# vyndej.net
KiCad netlist of a schematic drawn in EAGLE
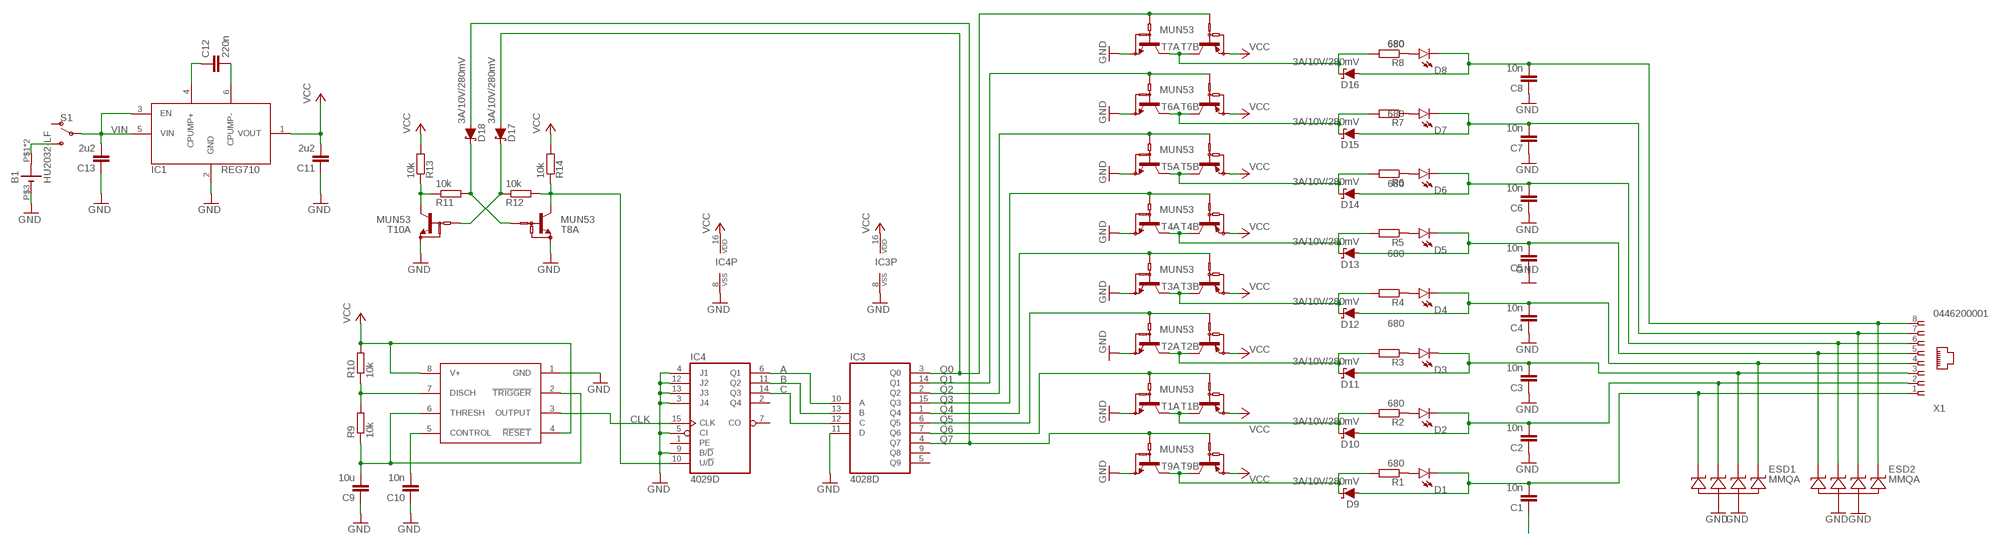
[diagram p0: schematic, sheet 1]

(export (version "E")
  (design (tool "Eeschema 10.0.6"))
  (components
    (comp (ref "B1")
      (value "HU2032-LF")
      (footprint "eagle-import:HU2032-LF")
      (libsource (lib "eagle-import") (part "HU2032-LF"))
    )
    (comp (ref "C1")
      (value "10n")
      (footprint "eagle-import:C0603")
      (libsource (lib "eagle-import") (part "C-EUC0603"))
    )
    (comp (ref "C2")
      (value "10n")
      (footprint "eagle-import:C0603")
      (libsource (lib "eagle-import") (part "C-EUC0603"))
    )
    (comp (ref "C3")
      (value "10n")
      (footprint "eagle-import:C0603")
      (libsource (lib "eagle-import") (part "C-EUC0603"))
    )
    (comp (ref "C4")
      (value "10n")
      (footprint "eagle-import:C0603")
      (libsource (lib "eagle-import") (part "C-EUC0603"))
    )
    (comp (ref "C5")
      (value "10n")
      (footprint "eagle-import:C0603")
      (libsource (lib "eagle-import") (part "C-EUC0603"))
    )
    (comp (ref "C6")
      (value "10n")
      (footprint "eagle-import:C0603")
      (libsource (lib "eagle-import") (part "C-EUC0603"))
    )
    (comp (ref "C7")
      (value "10n")
      (footprint "eagle-import:C0603")
      (libsource (lib "eagle-import") (part "C-EUC0603"))
    )
    (comp (ref "C8")
      (value "10n")
      (footprint "eagle-import:C0603")
      (libsource (lib "eagle-import") (part "C-EUC0603"))
    )
    (comp (ref "C9")
      (value "10u")
      (footprint "eagle-import:C1210K")
      (libsource (lib "eagle-import") (part "C-EUC1210K"))
    )
    (comp (ref "C10")
      (value "10n")
      (footprint "eagle-import:C0603")
      (libsource (lib "eagle-import") (part "C-EUC0603"))
    )
    (comp (ref "C11")
      (value "2u2")
      (footprint "eagle-import:C0603")
      (libsource (lib "eagle-import") (part "C-EUC0603"))
    )
    (comp (ref "C12")
      (value "220n")
      (footprint "eagle-import:C0603")
      (libsource (lib "eagle-import") (part "C-EUC0603"))
    )
    (comp (ref "C13")
      (value "2u2")
      (footprint "eagle-import:C0603")
      (libsource (lib "eagle-import") (part "C-EUC0603"))
    )
    (comp (ref "D1")
      (value "RED")
      (footprint "eagle-import:PLCC-2")
      (libsource (lib "eagle-import") (part "LED"))
    )
    (comp (ref "D2")
      (value "RED")
      (footprint "eagle-import:PLCC-2")
      (libsource (lib "eagle-import") (part "LED"))
    )
    (comp (ref "D3")
      (value "RED")
      (footprint "eagle-import:PLCC-2")
      (libsource (lib "eagle-import") (part "LED"))
    )
    (comp (ref "D4")
      (value "RED")
      (footprint "eagle-import:PLCC-2")
      (libsource (lib "eagle-import") (part "LED"))
    )
    (comp (ref "D5")
      (value "RED")
      (footprint "eagle-import:PLCC-2")
      (libsource (lib "eagle-import") (part "LED"))
    )
    (comp (ref "D6")
      (value "RED")
      (footprint "eagle-import:PLCC-2")
      (libsource (lib "eagle-import") (part "LED"))
    )
    (comp (ref "D7")
      (value "RED")
      (footprint "eagle-import:PLCC-2")
      (libsource (lib "eagle-import") (part "LED"))
    )
    (comp (ref "D8")
      (value "RED")
      (footprint "eagle-import:PLCC-2")
      (libsource (lib "eagle-import") (part "LED"))
    )
    (comp (ref "D9")
      (value "3A/10V/280mV")
      (footprint "eagle-import:SOD-323")
      (libsource (lib "eagle-import") (part "DIODE-SCHOTTKY-BAT60A"))
    )
    (comp (ref "D10")
      (value "3A/10V/280mV")
      (footprint "eagle-import:SOD-323")
      (libsource (lib "eagle-import") (part "DIODE-SCHOTTKY-BAT60A"))
    )
    (comp (ref "D11")
      (value "3A/10V/280mV")
      (footprint "eagle-import:SOD-323")
      (libsource (lib "eagle-import") (part "DIODE-SCHOTTKY-BAT60A"))
    )
    (comp (ref "D12")
      (value "3A/10V/280mV")
      (footprint "eagle-import:SOD-323")
      (libsource (lib "eagle-import") (part "DIODE-SCHOTTKY-BAT60A"))
    )
    (comp (ref "D13")
      (value "3A/10V/280mV")
      (footprint "eagle-import:SOD-323")
      (libsource (lib "eagle-import") (part "DIODE-SCHOTTKY-BAT60A"))
    )
    (comp (ref "D14")
      (value "3A/10V/280mV")
      (footprint "eagle-import:SOD-323")
      (libsource (lib "eagle-import") (part "DIODE-SCHOTTKY-BAT60A"))
    )
    (comp (ref "D15")
      (value "3A/10V/280mV")
      (footprint "eagle-import:SOD-323")
      (libsource (lib "eagle-import") (part "DIODE-SCHOTTKY-BAT60A"))
    )
    (comp (ref "D16")
      (value "3A/10V/280mV")
      (footprint "eagle-import:SOD-323")
      (libsource (lib "eagle-import") (part "DIODE-SCHOTTKY-BAT60A"))
    )
    (comp (ref "D17")
      (value "3A/10V/280mV")
      (footprint "eagle-import:SOD-323")
      (libsource (lib "eagle-import") (part "DIODE-SCHOTTKY-BAT60A"))
    )
    (comp (ref "D18")
      (value "3A/10V/280mV")
      (footprint "eagle-import:SOD-323")
      (libsource (lib "eagle-import") (part "DIODE-SCHOTTKY-BAT60A"))
    )
    (comp (ref "ESD1")
      (value "MMQA")
      (footprint "eagle-import:SC-74")
      (libsource (lib "eagle-import") (part "MMQA"))
    )
    (comp (ref "ESD2")
      (value "MMQA")
      (footprint "eagle-import:SC-74")
      (libsource (lib "eagle-import") (part "MMQA"))
    )
    (comp (ref "IC1")
      (value "REG710")
      (footprint "eagle-import:SOT23-6")
      (libsource (lib "eagle-import") (part "REG710"))
    )
    (comp (ref "IC2")
      (value "LMC555")
      (footprint "eagle-import:SO08")
      (libsource (lib "eagle-import") (part "LMC555"))
    )
    (comp (ref "IC3")
      (value "4028D")
      (footprint "eagle-import:SO16")
      (libsource (lib "eagle-import") (part "4028D"))
    )
    (comp (ref "IC4")
      (value "4029D")
      (footprint "eagle-import:SO16")
      (libsource (lib "eagle-import") (part "4029D"))
    )
    (comp (ref "R1")
      (value "680")
      (footprint "eagle-import:R0603")
      (libsource (lib "eagle-import") (part "R-EU_R0603"))
    )
    (comp (ref "R2")
      (value "680")
      (footprint "eagle-import:R0603")
      (libsource (lib "eagle-import") (part "R-EU_R0603"))
    )
    (comp (ref "R3")
      (value "680")
      (footprint "eagle-import:R0603")
      (libsource (lib "eagle-import") (part "R-EU_R0603"))
    )
    (comp (ref "R4")
      (value "680")
      (footprint "eagle-import:R0603")
      (libsource (lib "eagle-import") (part "R-EU_R0603"))
    )
    (comp (ref "R5")
      (value "680")
      (footprint "eagle-import:R0603")
      (libsource (lib "eagle-import") (part "R-EU_R0603"))
    )
    (comp (ref "R6")
      (value "680")
      (footprint "eagle-import:R0603")
      (libsource (lib "eagle-import") (part "R-EU_R0603"))
    )
    (comp (ref "R7")
      (value "680")
      (footprint "eagle-import:R0603")
      (libsource (lib "eagle-import") (part "R-EU_R0603"))
    )
    (comp (ref "R8")
      (value "680")
      (footprint "eagle-import:R0603")
      (libsource (lib "eagle-import") (part "R-EU_R0603"))
    )
    (comp (ref "R9")
      (value "10k")
      (footprint "eagle-import:R0603")
      (libsource (lib "eagle-import") (part "R-EU_R0603"))
    )
    (comp (ref "R10")
      (value "10k")
      (footprint "eagle-import:R0603")
      (libsource (lib "eagle-import") (part "R-EU_R0603"))
    )
    (comp (ref "R11")
      (value "10k")
      (footprint "eagle-import:R0603")
      (libsource (lib "eagle-import") (part "R-EU_R0603"))
    )
    (comp (ref "R12")
      (value "10k")
      (footprint "eagle-import:R0603")
      (libsource (lib "eagle-import") (part "R-EU_R0603"))
    )
    (comp (ref "R13")
      (value "10k")
      (footprint "eagle-import:R0603")
      (libsource (lib "eagle-import") (part "R-EU_R0603"))
    )
    (comp (ref "R14")
      (value "10k")
      (footprint "eagle-import:R0603")
      (libsource (lib "eagle-import") (part "R-EU_R0603"))
    )
    (comp (ref "S1")
      (value "SWITCH-SPDT-SMD-RIGHT-ANGLE")
      (footprint "eagle-import:SWITCH_SPST_SMD_A")
      (libsource (lib "eagle-import") (part "SWITCH-SPDT-SMD-RIGHT-ANGLE"))
    )
    (comp (ref "T1")
      (value "MUN53")
      (footprint "eagle-import:SOT-363")
      (libsource (lib "eagle-import") (part "MUN53"))
    )
    (comp (ref "T2")
      (value "MUN53")
      (footprint "eagle-import:SOT-363")
      (libsource (lib "eagle-import") (part "MUN53"))
    )
    (comp (ref "T3")
      (value "MUN53")
      (footprint "eagle-import:SOT-363")
      (libsource (lib "eagle-import") (part "MUN53"))
    )
    (comp (ref "T4")
      (value "MUN53")
      (footprint "eagle-import:SOT-363")
      (libsource (lib "eagle-import") (part "MUN53"))
    )
    (comp (ref "T5")
      (value "MUN53")
      (footprint "eagle-import:SOT-363")
      (libsource (lib "eagle-import") (part "MUN53"))
    )
    (comp (ref "T6")
      (value "MUN53")
      (footprint "eagle-import:SOT-363")
      (libsource (lib "eagle-import") (part "MUN53"))
    )
    (comp (ref "T7")
      (value "MUN53")
      (footprint "eagle-import:SOT-363")
      (libsource (lib "eagle-import") (part "MUN53"))
    )
    (comp (ref "T8")
      (value "MUN53")
      (footprint "eagle-import:SOT-363")
      (libsource (lib "eagle-import") (part "MUN53"))
    )
    (comp (ref "T9")
      (value "MUN53")
      (footprint "eagle-import:SOT-363")
      (libsource (lib "eagle-import") (part "MUN53"))
    )
    (comp (ref "T10")
      (value "MUN53")
      (footprint "eagle-import:SOT-363")
      (libsource (lib "eagle-import") (part "MUN53"))
    )
    (comp (ref "X1")
      (value "0446200001")
      (footprint "eagle-import:0446200001")
      (fields (field (name "MF") "MOLEX"))
      (libsource (lib "eagle-import") (part "0446200001"))
    )
  )
  (nets
    (net (code "1") (name "/A") (class "Default")
      (node (ref "IC3") (pin "10") (pinfunction "A_10") (pintype "input"))
      (node (ref "IC4") (pin "6") (pinfunction "Q1_6") (pintype "output"))
    )
    (net (code "2") (name "/B") (class "Default")
      (node (ref "IC3") (pin "13") (pinfunction "B_13") (pintype "input"))
      (node (ref "IC4") (pin "11") (pinfunction "Q2_11") (pintype "output"))
    )
    (net (code "3") (name "/C") (class "Default")
      (node (ref "IC3") (pin "12") (pinfunction "C_12") (pintype "input"))
      (node (ref "IC4") (pin "14") (pinfunction "Q3_14") (pintype "output"))
    )
    (net (code "4") (name "/CLK") (class "Default")
      (node (ref "IC2") (pin "3") (pinfunction "OUTPUT_3") (pintype "output"))
      (node (ref "IC4") (pin "15") (pinfunction "CLK_15") (pintype "input"))
    )
    (net (code "5") (name "/Q0") (class "Default")
      (node (ref "D17") (pin "A") (pinfunction "A_A") (pintype "passive"))
      (node (ref "IC3") (pin "3") (pinfunction "Q0_3") (pintype "output"))
      (node (ref "T7") (pin "P$2") (pinfunction "B_P$2") (pintype "passive"))
      (node (ref "T7") (pin "P$5") (pinfunction "B_P$5") (pintype "passive"))
    )
    (net (code "6") (name "/Q1") (class "Default")
      (node (ref "IC3") (pin "14") (pinfunction "Q1_14") (pintype "output"))
      (node (ref "T6") (pin "P$2") (pinfunction "B_P$2") (pintype "passive"))
      (node (ref "T6") (pin "P$5") (pinfunction "B_P$5") (pintype "passive"))
    )
    (net (code "7") (name "/Q2") (class "Default")
      (node (ref "IC3") (pin "2") (pinfunction "Q2_2") (pintype "output"))
      (node (ref "T5") (pin "P$2") (pinfunction "B_P$2") (pintype "passive"))
      (node (ref "T5") (pin "P$5") (pinfunction "B_P$5") (pintype "passive"))
    )
    (net (code "8") (name "/Q3") (class "Default")
      (node (ref "IC3") (pin "15") (pinfunction "Q3_15") (pintype "output"))
      (node (ref "T4") (pin "P$2") (pinfunction "B_P$2") (pintype "passive"))
      (node (ref "T4") (pin "P$5") (pinfunction "B_P$5") (pintype "passive"))
    )
    (net (code "9") (name "/Q4") (class "Default")
      (node (ref "IC3") (pin "1") (pinfunction "Q4_1") (pintype "output"))
      (node (ref "T3") (pin "P$2") (pinfunction "B_P$2") (pintype "passive"))
      (node (ref "T3") (pin "P$5") (pinfunction "B_P$5") (pintype "passive"))
    )
    (net (code "10") (name "/Q5") (class "Default")
      (node (ref "IC3") (pin "6") (pinfunction "Q5_6") (pintype "output"))
      (node (ref "T2") (pin "P$2") (pinfunction "B_P$2") (pintype "passive"))
      (node (ref "T2") (pin "P$5") (pinfunction "B_P$5") (pintype "passive"))
    )
    (net (code "11") (name "/Q6") (class "Default")
      (node (ref "IC3") (pin "7") (pinfunction "Q6_7") (pintype "output"))
      (node (ref "T1") (pin "P$2") (pinfunction "B_P$2") (pintype "passive"))
      (node (ref "T1") (pin "P$5") (pinfunction "B_P$5") (pintype "passive"))
    )
    (net (code "12") (name "/Q7") (class "Default")
      (node (ref "D18") (pin "A") (pinfunction "A_A") (pintype "passive"))
      (node (ref "IC3") (pin "4") (pinfunction "Q7_4") (pintype "output"))
      (node (ref "T9") (pin "P$2") (pinfunction "B_P$2") (pintype "passive"))
      (node (ref "T9") (pin "P$5") (pinfunction "B_P$5") (pintype "passive"))
    )
    (net (code "13") (name "/VIN") (class "Default")
      (node (ref "C13") (pin "2") (pinfunction "2_2") (pintype "passive"))
      (node (ref "IC1") (pin "3") (pinfunction "EN_3") (pintype "input"))
      (node (ref "IC1") (pin "5") (pinfunction "VIN_5") (pintype "power_in"))
      (node (ref "S1") (pin "2") (pinfunction "P_2") (pintype "passive"))
    )
    (net (code "14") (name "GND") (class "Default")
      (node (ref "B1") (pin "P$3") (pinfunction "-_P$3") (pintype "passive"))
      (node (ref "C10") (pin "1") (pinfunction "1_1") (pintype "passive"))
      (node (ref "C11") (pin "1") (pinfunction "1_1") (pintype "passive"))
      (node (ref "C13") (pin "1") (pinfunction "1_1") (pintype "passive"))
      (node (ref "C2") (pin "1") (pinfunction "1_1") (pintype "passive"))
      (node (ref "C3") (pin "1") (pinfunction "1_1") (pintype "passive"))
      (node (ref "C4") (pin "1") (pinfunction "1_1") (pintype "passive"))
      (node (ref "C5") (pin "1") (pinfunction "1_1") (pintype "passive"))
      (node (ref "C6") (pin "1") (pinfunction "1_1") (pintype "passive"))
      (node (ref "C7") (pin "1") (pinfunction "1_1") (pintype "passive"))
      (node (ref "C8") (pin "1") (pinfunction "1_1") (pintype "passive"))
      (node (ref "C9") (pin "1") (pinfunction "1_1") (pintype "passive"))
      (node (ref "ESD1") (pin "2") (pinfunction "A1_2") (pintype "passive"))
      (node (ref "ESD1") (pin "5") (pinfunction "A2_5") (pintype "passive"))
      (node (ref "ESD2") (pin "2") (pinfunction "A1_2") (pintype "passive"))
      (node (ref "ESD2") (pin "5") (pinfunction "A2_5") (pintype "passive"))
      (node (ref "IC1") (pin "2") (pinfunction "GND_2") (pintype "power_in"))
      (node (ref "IC2") (pin "1") (pinfunction "GND_1") (pintype "power_in"))
      (node (ref "IC3") (pin "11") (pinfunction "D_11") (pintype "input"))
      (node (ref "IC3") (pin "8") (pinfunction "VSS_8") (pintype "power_in"))
      (node (ref "IC4") (pin "12") (pinfunction "J2_12") (pintype "input"))
      (node (ref "IC4") (pin "13") (pinfunction "J3_13") (pintype "input"))
      (node (ref "IC4") (pin "3") (pinfunction "J4_3") (pintype "input"))
      (node (ref "IC4") (pin "4") (pinfunction "J1_4") (pintype "input"))
      (node (ref "IC4") (pin "5") (pinfunction "CI_5") (pintype "input"))
      (node (ref "IC4") (pin "8") (pinfunction "VSS_8") (pintype "power_in"))
      (node (ref "IC4") (pin "9") (pinfunction "B/~{D}_9") (pintype "input"))
      (node (ref "T1") (pin "P$1") (pinfunction "E_P$1") (pintype "passive"))
      (node (ref "T10") (pin "P$1") (pinfunction "E_P$1") (pintype "passive"))
      (node (ref "T2") (pin "P$1") (pinfunction "E_P$1") (pintype "passive"))
      (node (ref "T3") (pin "P$1") (pinfunction "E_P$1") (pintype "passive"))
      (node (ref "T4") (pin "P$1") (pinfunction "E_P$1") (pintype "passive"))
      (node (ref "T5") (pin "P$1") (pinfunction "E_P$1") (pintype "passive"))
      (node (ref "T6") (pin "P$1") (pinfunction "E_P$1") (pintype "passive"))
      (node (ref "T7") (pin "P$1") (pinfunction "E_P$1") (pintype "passive"))
      (node (ref "T8") (pin "P$1") (pinfunction "E_P$1") (pintype "passive"))
      (node (ref "T9") (pin "P$1") (pinfunction "E_P$1") (pintype "passive"))
    )
    (net (code "15") (name "Net-(D1-PadA)") (class "Default")
      (node (ref "D1") (pin "A") (pinfunction "A_A") (pintype "passive"))
      (node (ref "R1") (pin "1") (pinfunction "1_1") (pintype "passive"))
    )
    (net (code "16") (name "Net-(D2-PadA)") (class "Default")
      (node (ref "D2") (pin "A") (pinfunction "A_A") (pintype "passive"))
      (node (ref "R2") (pin "1") (pinfunction "1_1") (pintype "passive"))
    )
    (net (code "17") (name "Net-(D3-PadA)") (class "Default")
      (node (ref "D3") (pin "A") (pinfunction "A_A") (pintype "passive"))
      (node (ref "R3") (pin "1") (pinfunction "1_1") (pintype "passive"))
    )
    (net (code "18") (name "Net-(D4-PadA)") (class "Default")
      (node (ref "D4") (pin "A") (pinfunction "A_A") (pintype "passive"))
      (node (ref "R4") (pin "1") (pinfunction "1_1") (pintype "passive"))
    )
    (net (code "19") (name "Net-(D5-PadA)") (class "Default")
      (node (ref "D5") (pin "A") (pinfunction "A_A") (pintype "passive"))
      (node (ref "R5") (pin "1") (pinfunction "1_1") (pintype "passive"))
    )
    (net (code "20") (name "Net-(D6-PadA)") (class "Default")
      (node (ref "D6") (pin "A") (pinfunction "A_A") (pintype "passive"))
      (node (ref "R6") (pin "1") (pinfunction "1_1") (pintype "passive"))
    )
    (net (code "21") (name "Net-(D7-PadA)") (class "Default")
      (node (ref "D7") (pin "A") (pinfunction "A_A") (pintype "passive"))
      (node (ref "R7") (pin "1") (pinfunction "1_1") (pintype "passive"))
    )
    (net (code "22") (name "Net-(D8-PadA)") (class "Default")
      (node (ref "D8") (pin "A") (pinfunction "A_A") (pintype "passive"))
      (node (ref "R8") (pin "1") (pinfunction "1_1") (pintype "passive"))
    )
    (net (code "23") (name "Net-(ESD1-C)") (class "Default")
      (node (ref "C1") (pin "2") (pinfunction "2_2") (pintype "passive"))
      (node (ref "D1") (pin "C") (pinfunction "C_C") (pintype "passive"))
      (node (ref "D9") (pin "A") (pinfunction "A_A") (pintype "passive"))
      (node (ref "ESD1") (pin "1") (pinfunction "C_1") (pintype "passive"))
      (node (ref "X1") (pin "1") (pinfunction "1_1") (pintype "passive"))
    )
    (net (code "24") (name "Net-(ESD1-C1)") (class "Default")
      (node (ref "C2") (pin "2") (pinfunction "2_2") (pintype "passive"))
      (node (ref "D10") (pin "A") (pinfunction "A_A") (pintype "passive"))
      (node (ref "D2") (pin "C") (pinfunction "C_C") (pintype "passive"))
      (node (ref "ESD1") (pin "3") (pinfunction "C1_3") (pintype "passive"))
      (node (ref "X1") (pin "2") (pinfunction "2_2") (pintype "passive"))
    )
    (net (code "25") (name "Net-(ESD1-C2)") (class "Default")
      (node (ref "C3") (pin "2") (pinfunction "2_2") (pintype "passive"))
      (node (ref "D11") (pin "A") (pinfunction "A_A") (pintype "passive"))
      (node (ref "D3") (pin "C") (pinfunction "C_C") (pintype "passive"))
      (node (ref "ESD1") (pin "4") (pinfunction "C2_4") (pintype "passive"))
      (node (ref "X1") (pin "3") (pinfunction "3_3") (pintype "passive"))
    )
    (net (code "26") (name "Net-(ESD1-C3)") (class "Default")
      (node (ref "C4") (pin "2") (pinfunction "2_2") (pintype "passive"))
      (node (ref "D12") (pin "A") (pinfunction "A_A") (pintype "passive"))
      (node (ref "D4") (pin "C") (pinfunction "C_C") (pintype "passive"))
      (node (ref "ESD1") (pin "6") (pinfunction "C3_6") (pintype "passive"))
      (node (ref "X1") (pin "4") (pinfunction "4_4") (pintype "passive"))
    )
    (net (code "27") (name "Net-(ESD2-C)") (class "Default")
      (node (ref "C5") (pin "2") (pinfunction "2_2") (pintype "passive"))
      (node (ref "D13") (pin "A") (pinfunction "A_A") (pintype "passive"))
      (node (ref "D5") (pin "C") (pinfunction "C_C") (pintype "passive"))
      (node (ref "ESD2") (pin "1") (pinfunction "C_1") (pintype "passive"))
      (node (ref "X1") (pin "5") (pinfunction "5_5") (pintype "passive"))
    )
    (net (code "28") (name "Net-(ESD2-C1)") (class "Default")
      (node (ref "C6") (pin "2") (pinfunction "2_2") (pintype "passive"))
      (node (ref "D14") (pin "A") (pinfunction "A_A") (pintype "passive"))
      (node (ref "D6") (pin "C") (pinfunction "C_C") (pintype "passive"))
      (node (ref "ESD2") (pin "3") (pinfunction "C1_3") (pintype "passive"))
      (node (ref "X1") (pin "6") (pinfunction "6_6") (pintype "passive"))
    )
    (net (code "29") (name "Net-(ESD2-C2)") (class "Default")
      (node (ref "C7") (pin "2") (pinfunction "2_2") (pintype "passive"))
      (node (ref "D15") (pin "A") (pinfunction "A_A") (pintype "passive"))
      (node (ref "D7") (pin "C") (pinfunction "C_C") (pintype "passive"))
      (node (ref "ESD2") (pin "4") (pinfunction "C2_4") (pintype "passive"))
      (node (ref "X1") (pin "7") (pinfunction "7_7") (pintype "passive"))
    )
    (net (code "30") (name "Net-(ESD2-C3)") (class "Default")
      (node (ref "C8") (pin "2") (pinfunction "2_2") (pintype "passive"))
      (node (ref "D16") (pin "A") (pinfunction "A_A") (pintype "passive"))
      (node (ref "D8") (pin "C") (pinfunction "C_C") (pintype "passive"))
      (node (ref "ESD2") (pin "6") (pinfunction "C3_6") (pintype "passive"))
      (node (ref "X1") (pin "8") (pinfunction "8_8") (pintype "passive"))
    )
    (net (code "31") (name "Net-(IC1-CPUMP+)") (class "Default")
      (node (ref "C12") (pin "1") (pinfunction "1_1") (pintype "passive"))
      (node (ref "IC1") (pin "4") (pinfunction "CPUMP+_4") (pintype "bidirectional"))
    )
    (net (code "32") (name "Net-(IC1-CPUMP-)") (class "Default")
      (node (ref "C12") (pin "2") (pinfunction "2_2") (pintype "passive"))
      (node (ref "IC1") (pin "6") (pinfunction "CPUMP-_6") (pintype "bidirectional"))
    )
    (net (code "33") (name "Net-(IC2-CONTROL)") (class "Default")
      (node (ref "C10") (pin "2") (pinfunction "2_2") (pintype "passive"))
      (node (ref "IC2") (pin "5") (pinfunction "CONTROL_5") (pintype "bidirectional"))
    )
    (net (code "34") (name "Net-(IC2-DISCH)") (class "Default")
      (node (ref "IC2") (pin "7") (pinfunction "DISCH_7") (pintype "open_collector"))
      (node (ref "R10") (pin "1") (pinfunction "1_1") (pintype "passive"))
      (node (ref "R9") (pin "2") (pinfunction "2_2") (pintype "passive"))
    )
    (net (code "35") (name "Net-(IC2-THRESH)") (class "Default")
      (node (ref "C9") (pin "2") (pinfunction "2_2") (pintype "passive"))
      (node (ref "IC2") (pin "2") (pinfunction "~{TRIGGER}_2") (pintype "input"))
      (node (ref "IC2") (pin "6") (pinfunction "THRESH_6") (pintype "input"))
      (node (ref "R9") (pin "1") (pinfunction "1_1") (pintype "passive"))
    )
    (net (code "36") (name "Net-(IC4A-U{slash}~{D})") (class "Default")
      (node (ref "IC4") (pin "10") (pinfunction "U/~{D}_10") (pintype "input"))
      (node (ref "R12") (pin "2") (pinfunction "2_2") (pintype "passive"))
      (node (ref "R14") (pin "1") (pinfunction "1_1") (pintype "passive"))
      (node (ref "T8") (pin "P$6") (pinfunction "C_P$6") (pintype "passive"))
    )
    (net (code "37") (name "Net-(S1-S)") (class "Default")
      (node (ref "B1") (pin "P$1") (pinfunction "+_P$1") (pintype "passive"))
      (node (ref "B1") (pin "P$2") (pinfunction "+_P$2") (pintype "passive"))
      (node (ref "S1") (pin "3") (pinfunction "S_3") (pintype "passive"))
    )
    (net (code "38") (name "Net-(T1A-C)") (class "Default")
      (node (ref "D10") (pin "C") (pinfunction "C_C") (pintype "passive"))
      (node (ref "R2") (pin "2") (pinfunction "2_2") (pintype "passive"))
      (node (ref "T1") (pin "P$3") (pinfunction "C_P$3") (pintype "passive"))
      (node (ref "T1") (pin "P$6") (pinfunction "C_P$6") (pintype "passive"))
    )
    (net (code "39") (name "Net-(T2A-C)") (class "Default")
      (node (ref "D11") (pin "C") (pinfunction "C_C") (pintype "passive"))
      (node (ref "R3") (pin "2") (pinfunction "2_2") (pintype "passive"))
      (node (ref "T2") (pin "P$3") (pinfunction "C_P$3") (pintype "passive"))
      (node (ref "T2") (pin "P$6") (pinfunction "C_P$6") (pintype "passive"))
    )
    (net (code "40") (name "Net-(T3A-C)") (class "Default")
      (node (ref "D12") (pin "C") (pinfunction "C_C") (pintype "passive"))
      (node (ref "R4") (pin "2") (pinfunction "2_2") (pintype "passive"))
      (node (ref "T3") (pin "P$3") (pinfunction "C_P$3") (pintype "passive"))
      (node (ref "T3") (pin "P$6") (pinfunction "C_P$6") (pintype "passive"))
    )
    (net (code "41") (name "Net-(T4A-C)") (class "Default")
      (node (ref "D13") (pin "C") (pinfunction "C_C") (pintype "passive"))
      (node (ref "R5") (pin "2") (pinfunction "2_2") (pintype "passive"))
      (node (ref "T4") (pin "P$3") (pinfunction "C_P$3") (pintype "passive"))
      (node (ref "T4") (pin "P$6") (pinfunction "C_P$6") (pintype "passive"))
    )
    (net (code "42") (name "Net-(T5A-C)") (class "Default")
      (node (ref "D14") (pin "C") (pinfunction "C_C") (pintype "passive"))
      (node (ref "R6") (pin "2") (pinfunction "2_2") (pintype "passive"))
      (node (ref "T5") (pin "P$3") (pinfunction "C_P$3") (pintype "passive"))
      (node (ref "T5") (pin "P$6") (pinfunction "C_P$6") (pintype "passive"))
    )
    (net (code "43") (name "Net-(T6A-C)") (class "Default")
      (node (ref "D15") (pin "C") (pinfunction "C_C") (pintype "passive"))
      (node (ref "R7") (pin "2") (pinfunction "2_2") (pintype "passive"))
      (node (ref "T6") (pin "P$3") (pinfunction "C_P$3") (pintype "passive"))
      (node (ref "T6") (pin "P$6") (pinfunction "C_P$6") (pintype "passive"))
    )
    (net (code "44") (name "Net-(T7A-C)") (class "Default")
      (node (ref "D16") (pin "C") (pinfunction "C_C") (pintype "passive"))
      (node (ref "R8") (pin "2") (pinfunction "2_2") (pintype "passive"))
      (node (ref "T7") (pin "P$3") (pinfunction "C_P$3") (pintype "passive"))
      (node (ref "T7") (pin "P$6") (pinfunction "C_P$6") (pintype "passive"))
    )
    (net (code "45") (name "Net-(T8A-B)") (class "Default")
      (node (ref "D18") (pin "C") (pinfunction "C_C") (pintype "passive"))
      (node (ref "R11") (pin "2") (pinfunction "2_2") (pintype "passive"))
      (node (ref "T8") (pin "P$2") (pinfunction "B_P$2") (pintype "passive"))
    )
    (net (code "46") (name "Net-(T9A-C)") (class "Default")
      (node (ref "D9") (pin "C") (pinfunction "C_C") (pintype "passive"))
      (node (ref "R1") (pin "2") (pinfunction "2_2") (pintype "passive"))
      (node (ref "T9") (pin "P$3") (pinfunction "C_P$3") (pintype "passive"))
      (node (ref "T9") (pin "P$6") (pinfunction "C_P$6") (pintype "passive"))
    )
    (net (code "47") (name "Net-(T10A-B)") (class "Default")
      (node (ref "D17") (pin "C") (pinfunction "C_C") (pintype "passive"))
      (node (ref "R12") (pin "1") (pinfunction "1_1") (pintype "passive"))
      (node (ref "T10") (pin "P$2") (pinfunction "B_P$2") (pintype "passive"))
    )
    (net (code "48") (name "Net-(T10A-C)") (class "Default")
      (node (ref "R11") (pin "1") (pinfunction "1_1") (pintype "passive"))
      (node (ref "R13") (pin "1") (pinfunction "1_1") (pintype "passive"))
      (node (ref "T10") (pin "P$6") (pinfunction "C_P$6") (pintype "passive"))
    )
    (net (code "49") (name "VCC") (class "Default")
      (node (ref "C11") (pin "2") (pinfunction "2_2") (pintype "passive"))
      (node (ref "IC1") (pin "1") (pinfunction "VOUT_1") (pintype "power_in"))
      (node (ref "IC2") (pin "4") (pinfunction "~{RESET}_4") (pintype "input"))
      (node (ref "IC2") (pin "8") (pinfunction "V+_8") (pintype "power_in"))
      (node (ref "IC3") (pin "16") (pinfunction "VDD_16") (pintype "power_in"))
      (node (ref "IC4") (pin "16") (pinfunction "VDD_16") (pintype "power_in"))
      (node (ref "R10") (pin "2") (pinfunction "2_2") (pintype "passive"))
      (node (ref "R13") (pin "2") (pinfunction "2_2") (pintype "passive"))
      (node (ref "R14") (pin "2") (pinfunction "2_2") (pintype "passive"))
      (node (ref "T1") (pin "P$4") (pinfunction "E_P$4") (pintype "passive"))
      (node (ref "T2") (pin "P$4") (pinfunction "E_P$4") (pintype "passive"))
      (node (ref "T3") (pin "P$4") (pinfunction "E_P$4") (pintype "passive"))
      (node (ref "T4") (pin "P$4") (pinfunction "E_P$4") (pintype "passive"))
      (node (ref "T5") (pin "P$4") (pinfunction "E_P$4") (pintype "passive"))
      (node (ref "T6") (pin "P$4") (pinfunction "E_P$4") (pintype "passive"))
      (node (ref "T7") (pin "P$4") (pinfunction "E_P$4") (pintype "passive"))
      (node (ref "T9") (pin "P$4") (pinfunction "E_P$4") (pintype "passive"))
    )
    (net (code "50") (name "unconnected-(C1-Pad1)") (class "Default")
      (node (ref "C1") (pin "1") (pinfunction "1_1") (pintype "passive"))
    )
    (net (code "51") (name "unconnected-(IC3A-Q8-Pad9)") (class "Default")
      (node (ref "IC3") (pin "9") (pinfunction "Q8_9") (pintype "output"))
    )
    (net (code "52") (name "unconnected-(IC3A-Q9-Pad5)") (class "Default")
      (node (ref "IC3") (pin "5") (pinfunction "Q9_5") (pintype "output"))
    )
    (net (code "53") (name "unconnected-(IC4A-CO-Pad7)") (class "Default")
      (node (ref "IC4") (pin "7") (pinfunction "CO_7") (pintype "output"))
    )
    (net (code "54") (name "unconnected-(IC4A-PE-Pad1)") (class "Default")
      (node (ref "IC4") (pin "1") (pinfunction "PE_1") (pintype "input"))
    )
    (net (code "55") (name "unconnected-(IC4A-Q4-Pad2)") (class "Default")
      (node (ref "IC4") (pin "2") (pinfunction "Q4_2") (pintype "output"))
    )
    (net (code "56") (name "unconnected-(S1-O-Pad1)") (class "Default")
      (node (ref "S1") (pin "1") (pinfunction "O_1") (pintype "passive"))
    )
  )
)
